# v5-Power-Section-temp.net
KiCad netlist of a schematic drawn in EAGLE
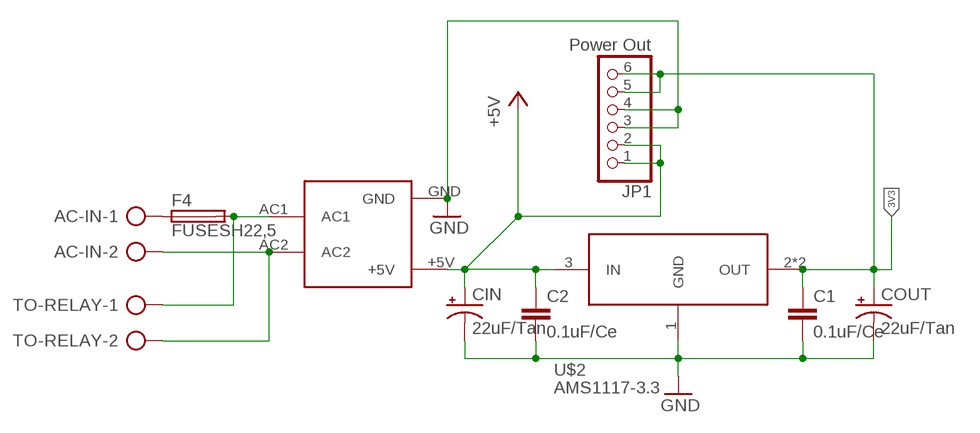
[diagram p0: schematic, sheet 1]

(export (version "E")
  (design (tool "Eeschema 10.0.6"))
  (components
    (comp (ref "AC-IN")
      (value "AK300/2")
      (footprint "eagle-import:AK300_2")
      (libsource (lib "eagle-import") (part "AK300/2"))
    )
    (comp (ref "C1")
      (value "0.1uF/Ce")
      (footprint "eagle-import:C025-024X044")
      (libsource (lib "eagle-import") (part "C-EU025-024X044"))
    )
    (comp (ref "C2")
      (value "0.1uF/Ce")
      (footprint "eagle-import:C025-024X044")
      (libsource (lib "eagle-import") (part "C-EU025-024X044"))
    )
    (comp (ref "CIN")
      (value "22uF/Tan")
      (footprint "eagle-import:E2,5-5")
      (libsource (lib "eagle-import") (part "CPOL-USE2.5-5"))
    )
    (comp (ref "COUT")
      (value "22uF/Tan")
      (footprint "eagle-import:E2,5-5")
      (libsource (lib "eagle-import") (part "CPOL-USE2.5-5"))
    )
    (comp (ref "F4")
      (value "FUSESH22,5")
      (footprint "eagle-import:SH22,5")
      (libsource (lib "eagle-import") (part "FUSESH22,5"))
    )
    (comp (ref "JP1")
      (value "Power Out")
      (footprint "eagle-import:1X06")
      (libsource (lib "eagle-import") (part "PINHD-1X6"))
    )
    (comp (ref "TO-RELAY")
      (value "AK300/2")
      (footprint "eagle-import:AK300_2")
      (libsource (lib "eagle-import") (part "AK300/2"))
    )
    (comp (ref "U$1")
      (value "HLK-PM01")
      (footprint "eagle-import:HLK-PM01")
      (libsource (lib "eagle-import") (part "HLK-PM01"))
    )
    (comp (ref "U$2")
      (value "AMS1117-3.3")
      (footprint "eagle-import:SOT-223")
      (libsource (lib "eagle-import") (part "AMS1117-3.3"))
    )
  )
  (nets
    (net (code "1") (name "+5V") (class "Default")
      (node (ref "C2") (pin "1") (pinfunction "1_1") (pintype "passive"))
      (node (ref "CIN") (pin "+") (pinfunction "+_+") (pintype "passive"))
      (node (ref "JP1") (pin "1") (pinfunction "1_1") (pintype "passive"))
      (node (ref "JP1") (pin "2") (pinfunction "2_2") (pintype "passive"))
      (node (ref "U$1") (pin "+5V") (pinfunction "+5V_+5V") (pintype "bidirectional"))
      (node (ref "U$2") (pin "3") (pinfunction "IN_3") (pintype "input"))
    )
    (net (code "2") (name "3V3") (class "Default")
      (node (ref "C1") (pin "1") (pinfunction "1_1") (pintype "passive"))
      (node (ref "COUT") (pin "+") (pinfunction "+_+") (pintype "passive"))
      (node (ref "JP1") (pin "5") (pinfunction "5_5") (pintype "passive"))
      (node (ref "JP1") (pin "6") (pinfunction "6_6") (pintype "passive"))
      (node (ref "U$2") (pin "2") (pinfunction "OUT_2") (pintype "output"))
      (node (ref "U$2") (pin "4") (pinfunction "OUT_4") (pintype "output"))
    )
    (net (code "3") (name "GND") (class "Default")
      (node (ref "C1") (pin "2") (pinfunction "2_2") (pintype "passive"))
      (node (ref "C2") (pin "2") (pinfunction "2_2") (pintype "passive"))
      (node (ref "CIN") (pin "-") (pinfunction "-_-") (pintype "passive"))
      (node (ref "COUT") (pin "-") (pinfunction "-_-") (pintype "passive"))
      (node (ref "JP1") (pin "3") (pinfunction "3_3") (pintype "passive"))
      (node (ref "JP1") (pin "4") (pinfunction "4_4") (pintype "passive"))
      (node (ref "U$1") (pin "GND") (pinfunction "GND_GND") (pintype "bidirectional"))
      (node (ref "U$2") (pin "1") (pinfunction "GND_1") (pintype "passive"))
    )
    (net (code "4") (name "Net-(AC-INA-KL)") (class "Default")
      (node (ref "AC-IN") (pin "1") (pinfunction "KL_1") (pintype "passive"))
      (node (ref "F4") (pin "1") (pinfunction "1_1") (pintype "passive"))
    )
    (net (code "5") (name "Net-(AC-INB-KL)") (class "Default")
      (node (ref "AC-IN") (pin "2") (pinfunction "KL_2") (pintype "passive"))
      (node (ref "TO-RELAY") (pin "2") (pinfunction "KL_2") (pintype "passive"))
      (node (ref "U$1") (pin "AC2") (pinfunction "AC2_AC2") (pintype "bidirectional"))
    )
    (net (code "6") (name "Net-(TO-RELAYA-KL)") (class "Default")
      (node (ref "F4") (pin "2") (pinfunction "2_2") (pintype "passive"))
      (node (ref "TO-RELAY") (pin "1") (pinfunction "KL_1") (pintype "passive"))
      (node (ref "U$1") (pin "AC1") (pinfunction "AC1_AC1") (pintype "bidirectional"))
    )
  )
)
